# 10MHzRefOsc_2V3.net
KiCad netlist of a schematic drawn in EAGLE
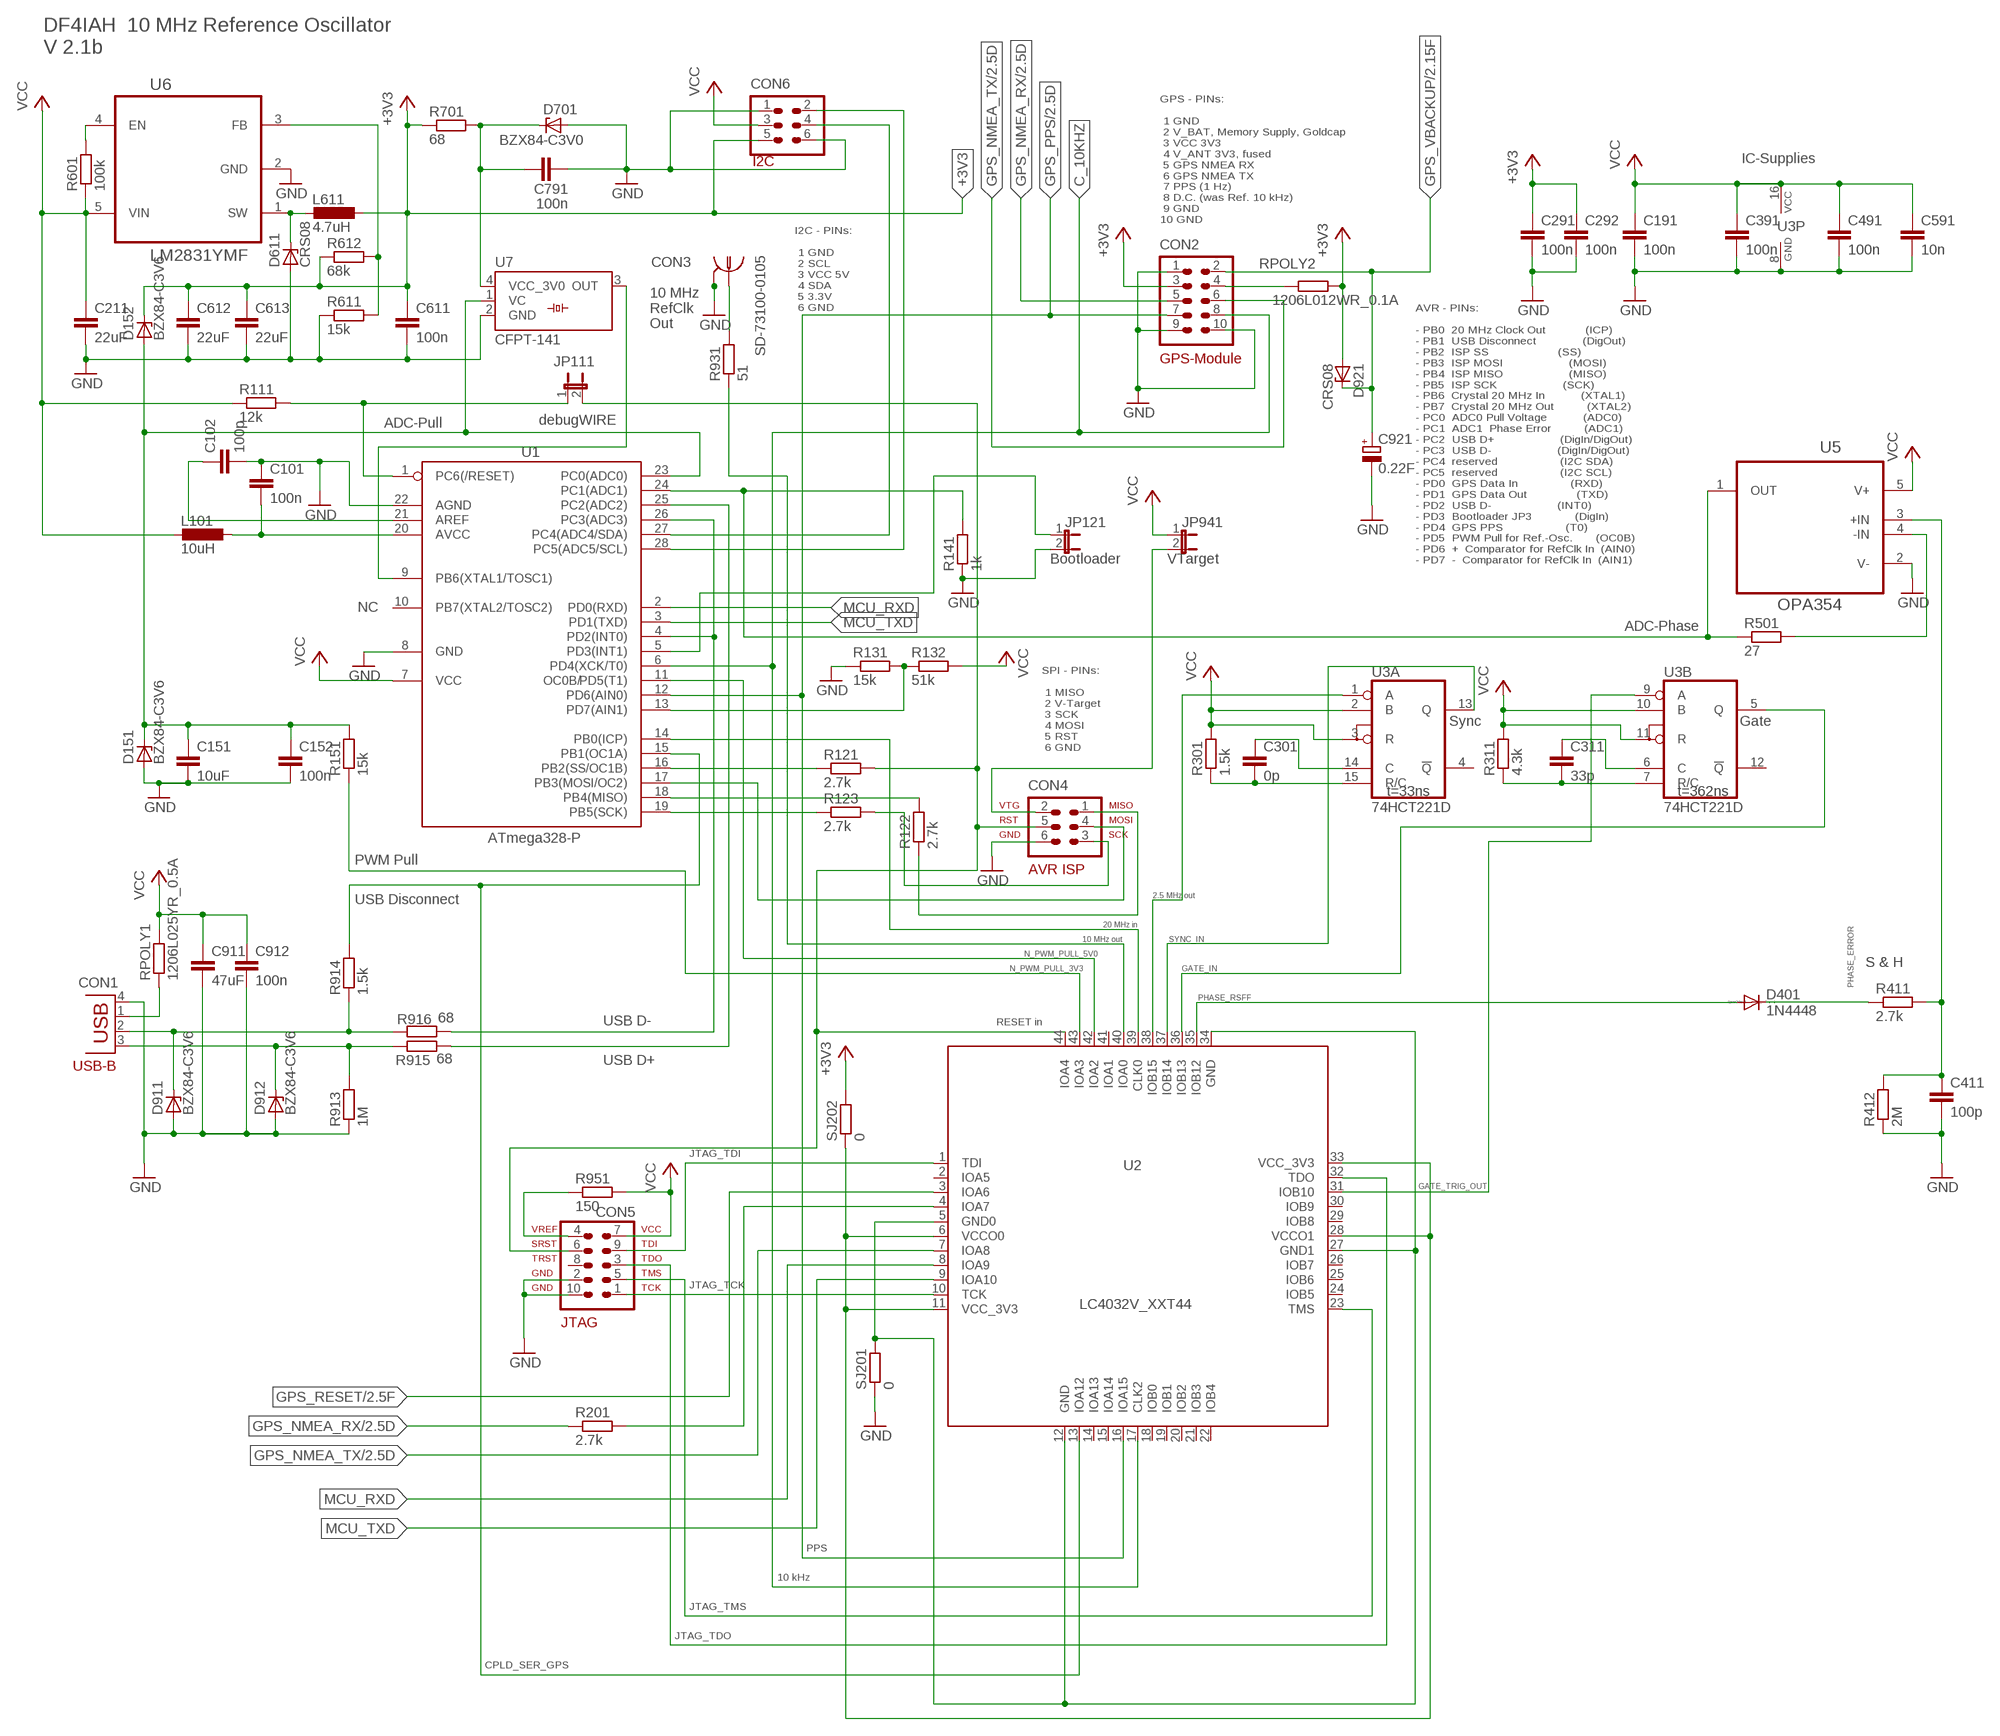
[diagram p0: schematic, sheet 1]
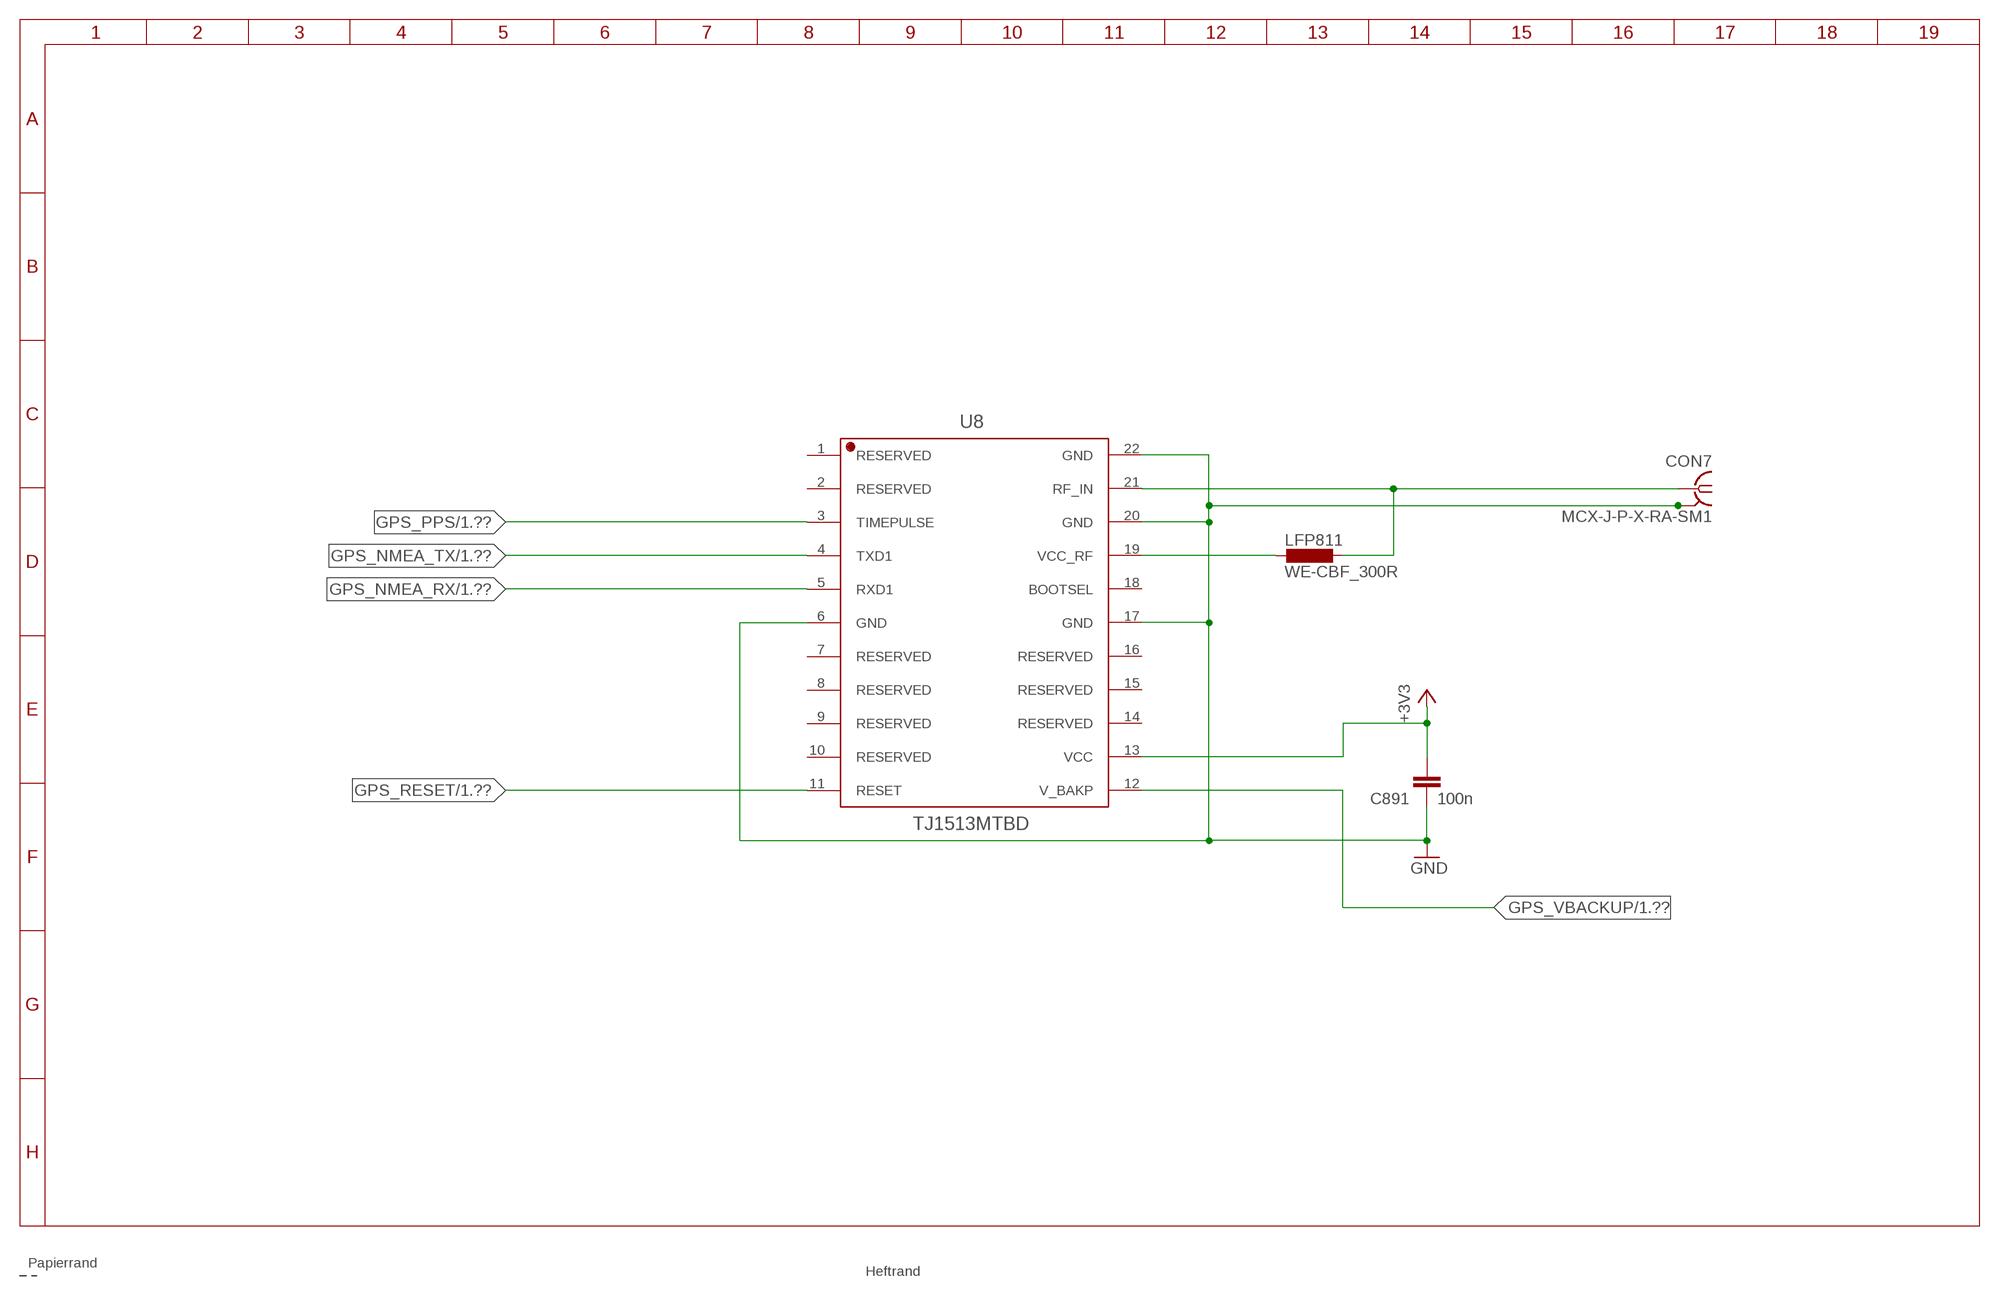
[diagram p1: schematic, sheet 2]
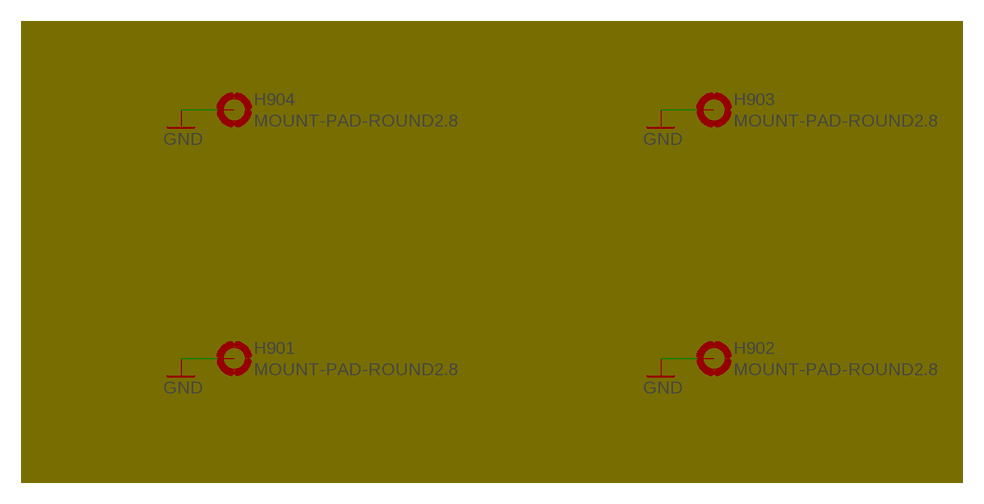
[diagram p2: schematic, sheet 3]

(export (version "E")
  (design (tool "Eeschema 10.0.6"))
  (components
    (comp (ref "H901")
      (value "MOUNT-PAD-ROUND2.8")
      (footprint "eagle-import:2,8-PAD")
      (libsource (lib "eagle-import") (part "MOUNT-PAD-ROUND2.8"))
    )
    (comp (ref "H902")
      (value "MOUNT-PAD-ROUND2.8")
      (footprint "eagle-import:2,8-PAD")
      (libsource (lib "eagle-import") (part "MOUNT-PAD-ROUND2.8"))
    )
    (comp (ref "H903")
      (value "MOUNT-PAD-ROUND2.8")
      (footprint "eagle-import:2,8-PAD")
      (libsource (lib "eagle-import") (part "MOUNT-PAD-ROUND2.8"))
    )
    (comp (ref "H904")
      (value "MOUNT-PAD-ROUND2.8")
      (footprint "eagle-import:2,8-PAD")
      (libsource (lib "eagle-import") (part "MOUNT-PAD-ROUND2.8"))
    )
    (comp (ref "C891")
      (value "100n")
      (footprint "eagle-import:C0805")
      (libsource (lib "eagle-import") (part "C-EUC0805"))
    )
    (comp (ref "CON7")
      (value "MCX-J-P-X-RA-SM1")
      (footprint "eagle-import:MCX-J-P-X-RA-SM1")
      (libsource (lib "eagle-import") (part "MCX-J-P-X-RA-SM1"))
    )
    (comp (ref "LFP811")
      (value "WE-CBF_300R")
      (footprint "eagle-import:L3216C")
      (libsource (lib "eagle-import") (part "L-EUL3216C"))
    )
    (comp (ref "U8")
      (value "TJ1513MTBD")
      (footprint "eagle-import:TJ1513MTBD")
      (libsource (lib "eagle-import") (part "TJ1513MTBD"))
    )
    (comp (ref "C101")
      (value "100n")
      (footprint "eagle-import:C0805")
      (libsource (lib "eagle-import") (part "rcl_C-EUC0805"))
    )
    (comp (ref "C102")
      (value "100p")
      (footprint "eagle-import:C0805")
      (libsource (lib "eagle-import") (part "rcl_C-EUC0805"))
    )
    (comp (ref "C151")
      (value "10uF")
      (footprint "eagle-import:C0805")
      (libsource (lib "eagle-import") (part "rcl_C-EUC0805"))
    )
    (comp (ref "C152")
      (value "100n")
      (footprint "eagle-import:C0805")
      (libsource (lib "eagle-import") (part "rcl_C-EUC0805"))
    )
    (comp (ref "C191")
      (value "100n")
      (footprint "eagle-import:C0805")
      (libsource (lib "eagle-import") (part "rcl_C-EUC0805"))
    )
    (comp (ref "C211")
      (value "22uF")
      (footprint "eagle-import:C0805")
      (libsource (lib "eagle-import") (part "rcl_C-EUC0805"))
    )
    (comp (ref "C291")
      (value "100n")
      (footprint "eagle-import:C0805")
      (libsource (lib "eagle-import") (part "rcl_C-EUC0805"))
    )
    (comp (ref "C292")
      (value "100n")
      (footprint "eagle-import:C0805")
      (libsource (lib "eagle-import") (part "rcl_C-EUC0805"))
    )
    (comp (ref "C301")
      (value "0p")
      (footprint "eagle-import:C0805")
      (libsource (lib "eagle-import") (part "rcl_C-EUC0805"))
    )
    (comp (ref "C311")
      (value "33p")
      (footprint "eagle-import:C0805")
      (libsource (lib "eagle-import") (part "rcl_C-EUC0805"))
    )
    (comp (ref "C391")
      (value "100n")
      (footprint "eagle-import:C0805")
      (libsource (lib "eagle-import") (part "rcl_C-EUC0805"))
    )
    (comp (ref "C411")
      (value "100p")
      (footprint "eagle-import:C0805")
      (libsource (lib "eagle-import") (part "rcl_C-EUC0805"))
    )
    (comp (ref "C491")
      (value "100n")
      (footprint "eagle-import:C0805")
      (libsource (lib "eagle-import") (part "rcl_C-EUC0805"))
    )
    (comp (ref "C591")
      (value "10n")
      (footprint "eagle-import:C0805")
      (libsource (lib "eagle-import") (part "rcl_C-EUC0805"))
    )
    (comp (ref "C611")
      (value "100n")
      (footprint "eagle-import:C0805")
      (libsource (lib "eagle-import") (part "rcl_C-EUC0805"))
    )
    (comp (ref "C612")
      (value "22uF")
      (footprint "eagle-import:C0805")
      (libsource (lib "eagle-import") (part "rcl_C-EUC0805"))
    )
    (comp (ref "C613")
      (value "22uF")
      (footprint "eagle-import:C0805")
      (libsource (lib "eagle-import") (part "rcl_C-EUC0805"))
    )
    (comp (ref "C791")
      (value "100n")
      (footprint "eagle-import:C0805")
      (libsource (lib "eagle-import") (part "rcl_C-EUC0805"))
    )
    (comp (ref "C911")
      (value "47uF")
      (footprint "eagle-import:C0805")
      (libsource (lib "eagle-import") (part "rcl_C-EUC0805"))
    )
    (comp (ref "C912")
      (value "100n")
      (footprint "eagle-import:C0805")
      (libsource (lib "eagle-import") (part "rcl_C-EUC0805"))
    )
    (comp (ref "C921")
      (value "0.22F")
      (footprint "eagle-import:140CLH-1010")
      (libsource (lib "eagle-import") (part "CPOL-EU140CLH-1010"))
    )
    (comp (ref "CON1")
      (value "TYCO-AMP_USBUSB-B_SMT")
      (footprint "eagle-import:TYCO-AMP_USB-B_SMT")
      (fields (field (name "MF") "TYCO-AMP") (field (name "MPN") "1734346"))
      (libsource (lib "eagle-import") (part "TYCO-AMP_USBUSB-B_SMT"))
    )
    (comp (ref "CON2")
      (value "HEADER-2X5SMD")
      (footprint "eagle-import:2X5SMD")
      (libsource (lib "eagle-import") (part "HEADER-2X5SMD"))
    )
    (comp (ref "CON3")
      (value "SD-73100-0105")
      (footprint "eagle-import:MOLEX_BNC-JACK-50R_SD-73100-0105")
      (fields (field (name "MF") "MOLEX"))
      (libsource (lib "eagle-import") (part "MOLEX_BNC-JACK-50R_SD-73100-0105"))
    )
    (comp (ref "CON4")
      (value "AVR-ISP-6SMD")
      (footprint "eagle-import:2X3SMD")
      (libsource (lib "eagle-import") (part "AVR-ISP-6SMD"))
    )
    (comp (ref "CON5")
      (value "AVR-JTAG-10SMD")
      (footprint "eagle-import:2X5SMD")
      (libsource (lib "eagle-import") (part "AVR-JTAG-10SMD"))
    )
    (comp (ref "CON6")
      (value "HEADER-2X3SMD")
      (footprint "eagle-import:2X03SMD")
      (libsource (lib "eagle-import") (part "HEADER-2X3SMD"))
    )
    (comp (ref "D151")
      (value "BZX84-C3V6")
      (footprint "eagle-import:TO236")
      (libsource (lib "eagle-import") (part "BZX84CSMD"))
    )
    (comp (ref "D152")
      (value "BZX84-C3V6")
      (footprint "eagle-import:TO236")
      (libsource (lib "eagle-import") (part "BZX84CSMD"))
    )
    (comp (ref "D401")
      (value "1N4448")
      (footprint "eagle-import:SOD123")
      (libsource (lib "eagle-import") (part "DIODE-SOD123"))
    )
    (comp (ref "D611")
      (value "CRS08")
      (footprint "eagle-import:SOD80C")
      (libsource (lib "eagle-import") (part "ZENER-DIODESOD80C"))
    )
    (comp (ref "D701")
      (value "BZX84-C3V0")
      (footprint "eagle-import:TO236")
      (libsource (lib "eagle-import") (part "BZX84CSMD"))
    )
    (comp (ref "D911")
      (value "BZX84-C3V6")
      (footprint "eagle-import:TO236")
      (libsource (lib "eagle-import") (part "BZX84CSMD"))
    )
    (comp (ref "D912")
      (value "BZX84-C3V6")
      (footprint "eagle-import:TO236")
      (libsource (lib "eagle-import") (part "BZX84CSMD"))
    )
    (comp (ref "D921")
      (value "CRS08")
      (footprint "eagle-import:SOD80C")
      (libsource (lib "eagle-import") (part "ZENER-DIODESOD80C"))
    )
    (comp (ref "JP111")
      (value "JP1E")
      (footprint "eagle-import:JP1")
      (libsource (lib "eagle-import") (part "JP1E"))
    )
    (comp (ref "JP121")
      (value "JP1E")
      (footprint "eagle-import:JP1")
      (libsource (lib "eagle-import") (part "JP1E"))
    )
    (comp (ref "JP941")
      (value "JP1E")
      (footprint "eagle-import:JP1")
      (libsource (lib "eagle-import") (part "JP1E"))
    )
    (comp (ref "L101")
      (value "10uH")
      (footprint "eagle-import:L1812")
      (libsource (lib "eagle-import") (part "rcl_L-EUL1812"))
    )
    (comp (ref "L611")
      (value "4.7uH")
      (footprint "eagle-import:L5650M")
      (libsource (lib "eagle-import") (part "rcl_L-EUL5650M"))
    )
    (comp (ref "R111")
      (value "12k")
      (footprint "eagle-import:R0805")
      (libsource (lib "eagle-import") (part "R-EU_R0805"))
    )
    (comp (ref "R121")
      (value "2.7k")
      (footprint "eagle-import:R0805")
      (libsource (lib "eagle-import") (part "R-EU_R0805"))
    )
    (comp (ref "R122")
      (value "2.7k")
      (footprint "eagle-import:R0805")
      (libsource (lib "eagle-import") (part "R-EU_R0805"))
    )
    (comp (ref "R123")
      (value "2.7k")
      (footprint "eagle-import:R0805")
      (libsource (lib "eagle-import") (part "R-EU_R0805"))
    )
    (comp (ref "R131")
      (value "15k")
      (footprint "eagle-import:R0805")
      (libsource (lib "eagle-import") (part "R-EU_R0805"))
    )
    (comp (ref "R132")
      (value "51k")
      (footprint "eagle-import:R0805")
      (libsource (lib "eagle-import") (part "R-EU_R0805"))
    )
    (comp (ref "R141")
      (value "1k")
      (footprint "eagle-import:R0805")
      (libsource (lib "eagle-import") (part "R-EU_R0805"))
    )
    (comp (ref "R151")
      (value "15k")
      (footprint "eagle-import:R0805")
      (libsource (lib "eagle-import") (part "R-EU_R0805"))
    )
    (comp (ref "R201")
      (value "2.7k")
      (footprint "eagle-import:R0805")
      (libsource (lib "eagle-import") (part "R-EU_R0805"))
    )
    (comp (ref "R301")
      (value "1.5k")
      (footprint "eagle-import:R0805")
      (libsource (lib "eagle-import") (part "R-EU_R0805"))
    )
    (comp (ref "R311")
      (value "4.3k")
      (footprint "eagle-import:R0805")
      (libsource (lib "eagle-import") (part "R-EU_R0805"))
    )
    (comp (ref "R411")
      (value "2.7k")
      (footprint "eagle-import:R0805")
      (libsource (lib "eagle-import") (part "R-EU_R0805"))
    )
    (comp (ref "R412")
      (value "2M")
      (footprint "eagle-import:R0805")
      (libsource (lib "eagle-import") (part "R-EU_R0805"))
    )
    (comp (ref "R501")
      (value "27")
      (footprint "eagle-import:R0805")
      (libsource (lib "eagle-import") (part "R-EU_R0805"))
    )
    (comp (ref "R601")
      (value "100k")
      (footprint "eagle-import:R0805")
      (libsource (lib "eagle-import") (part "R-EU_R0805"))
    )
    (comp (ref "R611")
      (value "15k")
      (footprint "eagle-import:R0805")
      (libsource (lib "eagle-import") (part "R-EU_R0805"))
    )
    (comp (ref "R612")
      (value "68k")
      (footprint "eagle-import:R0805")
      (libsource (lib "eagle-import") (part "R-EU_R0805"))
    )
    (comp (ref "R701")
      (value "68")
      (footprint "eagle-import:R0805")
      (libsource (lib "eagle-import") (part "R-EU_R0805"))
    )
    (comp (ref "R913")
      (value "1M")
      (footprint "eagle-import:R0805")
      (libsource (lib "eagle-import") (part "R-EU_R0805"))
    )
    (comp (ref "R914")
      (value "1.5k")
      (footprint "eagle-import:R0805")
      (libsource (lib "eagle-import") (part "R-EU_R0805"))
    )
    (comp (ref "R915")
      (value "68")
      (footprint "eagle-import:R0805")
      (libsource (lib "eagle-import") (part "R-EU_R0805"))
    )
    (comp (ref "R916")
      (value "68")
      (footprint "eagle-import:R0805")
      (libsource (lib "eagle-import") (part "R-EU_R0805"))
    )
    (comp (ref "R931")
      (value "51")
      (footprint "eagle-import:R0805")
      (libsource (lib "eagle-import") (part "R-EU_R0805"))
    )
    (comp (ref "R951")
      (value "150")
      (footprint "eagle-import:R0805")
      (libsource (lib "eagle-import") (part "R-EU_R0805"))
    )
    (comp (ref "RPOLY1")
      (value "1206L025YR_0.5A")
      (footprint "eagle-import:M1206")
      (libsource (lib "eagle-import") (part "R-EU_M1206"))
    )
    (comp (ref "RPOLY2")
      (value "1206L012WR_0.1A")
      (footprint "eagle-import:M1206")
      (libsource (lib "eagle-import") (part "R-EU_M1206"))
    )
    (comp (ref "SJ201")
      (value "0")
      (footprint "eagle-import:R0805")
      (libsource (lib "eagle-import") (part "R-EU_R0805"))
    )
    (comp (ref "SJ202")
      (value "0")
      (footprint "eagle-import:R0805")
      (libsource (lib "eagle-import") (part "R-EU_R0805"))
    )
    (comp (ref "U1")
      (value "ATmega328-P")
      (footprint "eagle-import:DIL28-3")
      (libsource (lib "eagle-import") (part "MEGA8-P"))
    )
    (comp (ref "U2")
      (value "LC4032V_XXT44")
      (footprint "eagle-import:TQFP44")
      (libsource (lib "eagle-import") (part "LC4032V_XXT44"))
    )
    (comp (ref "U3")
      (value "74HCT221D")
      (footprint "eagle-import:SO16")
      (libsource (lib "eagle-import") (part "74221DHCT"))
    )
    (comp (ref "U5")
      (value "OPA354")
      (footprint "eagle-import:SOT-23-5")
      (fields (field (name "MPN") "OPA354AIDBVT"))
      (libsource (lib "eagle-import") (part "OPA354"))
    )
    (comp (ref "U6")
      (value "LM2831YMF")
      (footprint "eagle-import:SOT95P280X145-5N")
      (fields (field (name "MPN") "LM2831YMF/NOPB"))
      (libsource (lib "eagle-import") (part "LM2831YMF"))
    )
    (comp (ref "U7")
      (value "CFPT-141")
      (footprint "eagle-import:CFPT-141")
      (fields (field (name "MF") "IQD-FREQUENCY-PRODUCTS") (field (name "MPN") "LFTVXO022175"))
      (libsource (lib "eagle-import") (part "CFPT-141"))
    )
  )
  (nets
    (net (code "1") (name "+3V3") (class "Default")
      (node (ref "C291") (pin "1") (pinfunction "1_1") (pintype "passive"))
      (node (ref "C292") (pin "1") (pinfunction "1_1") (pintype "passive"))
      (node (ref "C611") (pin "1") (pinfunction "1_1") (pintype "passive"))
      (node (ref "C612") (pin "1") (pinfunction "1_1") (pintype "passive"))
      (node (ref "C613") (pin "1") (pinfunction "1_1") (pintype "passive"))
      (node (ref "C891") (pin "1") (pinfunction "1_1") (pintype "passive"))
      (node (ref "CON2") (pin "3") (pinfunction "3_3") (pintype "passive"))
      (node (ref "CON6") (pin "5") (pinfunction "5_5") (pintype "passive"))
      (node (ref "D152") (pin "C") (pinfunction "C_C") (pintype "passive"))
      (node (ref "D921") (pin "A") (pinfunction "A_A") (pintype "passive"))
      (node (ref "L611") (pin "1") (pinfunction "1_1") (pintype "passive"))
      (node (ref "R612") (pin "1") (pinfunction "1_1") (pintype "passive"))
      (node (ref "R701") (pin "1") (pinfunction "1_1") (pintype "passive"))
      (node (ref "RPOLY2") (pin "2") (pinfunction "2_2") (pintype "passive"))
      (node (ref "SJ202") (pin "2") (pinfunction "2_2") (pintype "passive"))
      (node (ref "U8") (pin "13") (pinfunction "VCC_13") (pintype "power_in"))
    )
    (net (code "2") (name "C_10KHZ") (class "Default")
      (node (ref "CON2") (pin "8") (pinfunction "8_8") (pintype "passive"))
      (node (ref "U1") (pin "6") (pinfunction "PD4(XCK/T0)_6") (pintype "bidirectional"))
      (node (ref "U2") (pin "17") (pinfunction "CLK2_17") (pintype "input"))
    )
    (net (code "3") (name "GATE_IN") (class "Default")
      (node (ref "U2") (pin "36") (pinfunction "IOB13_36") (pintype "bidirectional"))
      (node (ref "U3") (pin "5") (pinfunction "Q_5") (pintype "output"))
    )
    (net (code "4") (name "GATE_TRIG_OUT") (class "Default")
      (node (ref "U2") (pin "31") (pinfunction "IOB10_31") (pintype "bidirectional"))
      (node (ref "U3") (pin "9") (pinfunction "A_9") (pintype "input"))
    )
    (net (code "5") (name "GND") (class "Default")
      (node (ref "C101") (pin "1") (pinfunction "1_1") (pintype "passive"))
      (node (ref "C102") (pin "2") (pinfunction "2_2") (pintype "passive"))
      (node (ref "C151") (pin "2") (pinfunction "2_2") (pintype "passive"))
      (node (ref "C152") (pin "2") (pinfunction "2_2") (pintype "passive"))
      (node (ref "C191") (pin "2") (pinfunction "2_2") (pintype "passive"))
      (node (ref "C211") (pin "2") (pinfunction "2_2") (pintype "passive"))
      (node (ref "C291") (pin "2") (pinfunction "2_2") (pintype "passive"))
      (node (ref "C292") (pin "2") (pinfunction "2_2") (pintype "passive"))
      (node (ref "C391") (pin "2") (pinfunction "2_2") (pintype "passive"))
      (node (ref "C411") (pin "2") (pinfunction "2_2") (pintype "passive"))
      (node (ref "C491") (pin "2") (pinfunction "2_2") (pintype "passive"))
      (node (ref "C591") (pin "2") (pinfunction "2_2") (pintype "passive"))
      (node (ref "C611") (pin "2") (pinfunction "2_2") (pintype "passive"))
      (node (ref "C612") (pin "2") (pinfunction "2_2") (pintype "passive"))
      (node (ref "C613") (pin "2") (pinfunction "2_2") (pintype "passive"))
      (node (ref "C791") (pin "2") (pinfunction "2_2") (pintype "passive"))
      (node (ref "C891") (pin "2") (pinfunction "2_2") (pintype "passive"))
      (node (ref "C911") (pin "2") (pinfunction "2_2") (pintype "passive"))
      (node (ref "C912") (pin "2") (pinfunction "2_2") (pintype "passive"))
      (node (ref "C921") (pin "-") (pinfunction "-_-") (pintype "passive"))
      (node (ref "CON1") (pin "4") (pinfunction "GND_4") (pintype "bidirectional"))
      (node (ref "CON2") (pin "1") (pinfunction "1_1") (pintype "passive"))
      (node (ref "CON2") (pin "10") (pinfunction "10_10") (pintype "passive"))
      (node (ref "CON2") (pin "9") (pinfunction "9_9") (pintype "passive"))
      (node (ref "CON3") (pin "2") (pinfunction "2_2") (pintype "passive"))
      (node (ref "CON3") (pin "3") (pinfunction "3_3") (pintype "passive"))
      (node (ref "CON4") (pin "6") (pinfunction "6_6") (pintype "passive"))
      (node (ref "CON5") (pin "10") (pinfunction "10_10") (pintype "passive"))
      (node (ref "CON5") (pin "2") (pinfunction "2_2") (pintype "passive"))
      (node (ref "CON6") (pin "1") (pinfunction "1_1") (pintype "passive"))
      (node (ref "CON6") (pin "6") (pinfunction "6_6") (pintype "passive"))
      (node (ref "CON7") (pin "2") (pinfunction "2_2") (pintype "passive"))
      (node (ref "CON7") (pin "3") (pinfunction "3_3") (pintype "passive"))
      (node (ref "CON7") (pin "4") (pinfunction "4_4") (pintype "passive"))
      (node (ref "CON7") (pin "5") (pinfunction "5_5") (pintype "passive"))
      (node (ref "D151") (pin "A") (pinfunction "A_A") (pintype "passive"))
      (node (ref "D611") (pin "A") (pinfunction "A_A") (pintype "passive"))
      (node (ref "D701") (pin "A") (pinfunction "A_A") (pintype "passive"))
      (node (ref "D911") (pin "A") (pinfunction "A_A") (pintype "passive"))
      (node (ref "D912") (pin "A") (pinfunction "A_A") (pintype "passive"))
      (node (ref "H901") (pin "B2,8") (pinfunction "MOUNT_B2,8") (pintype "passive"))
      (node (ref "H902") (pin "B2,8") (pinfunction "MOUNT_B2,8") (pintype "passive"))
      (node (ref "H903") (pin "B2,8") (pinfunction "MOUNT_B2,8") (pintype "passive"))
      (node (ref "H904") (pin "B2,8") (pinfunction "MOUNT_B2,8") (pintype "passive"))
      (node (ref "JP121") (pin "2") (pinfunction "2_2") (pintype "passive"))
      (node (ref "R131") (pin "1") (pinfunction "1_1") (pintype "passive"))
      (node (ref "R141") (pin "1") (pinfunction "1_1") (pintype "passive"))
      (node (ref "R412") (pin "1") (pinfunction "1_1") (pintype "passive"))
      (node (ref "R611") (pin "1") (pinfunction "1_1") (pintype "passive"))
      (node (ref "R913") (pin "1") (pinfunction "1_1") (pintype "passive"))
      (node (ref "SJ201") (pin "1") (pinfunction "1_1") (pintype "passive"))
      (node (ref "U1") (pin "22") (pinfunction "AGND_22") (pintype "bidirectional"))
      (node (ref "U1") (pin "8") (pinfunction "GND_8") (pintype "bidirectional"))
      (node (ref "U3") (pin "8") (pinfunction "GND_8") (pintype "power_in"))
      (node (ref "U5") (pin "2") (pinfunction "V-_2") (pintype "power_in"))
      (node (ref "U6") (pin "2") (pinfunction "GND_2") (pintype "passive"))
      (node (ref "U7") (pin "2") (pinfunction "GND_2") (pintype "power_in"))
      (node (ref "U8") (pin "17") (pinfunction "GND_17") (pintype "power_in"))
      (node (ref "U8") (pin "20") (pinfunction "GND_20") (pintype "power_in"))
      (node (ref "U8") (pin "22") (pinfunction "GND_22") (pintype "power_in"))
      (node (ref "U8") (pin "6") (pinfunction "GND_6") (pintype "power_in"))
    )
    (net (code "6") (name "GPS_NMEA_RX") (class "Default")
      (node (ref "CON2") (pin "5") (pinfunction "5_5") (pintype "passive"))
      (node (ref "R201") (pin "1") (pinfunction "1_1") (pintype "passive"))
      (node (ref "U8") (pin "5") (pinfunction "RXD1_5") (pintype "input"))
    )
    (net (code "7") (name "GPS_NMEA_TX") (class "Default")
      (node (ref "CON2") (pin "6") (pinfunction "6_6") (pintype "passive"))
      (node (ref "U2") (pin "7") (pinfunction "IOA8_7") (pintype "bidirectional"))
      (node (ref "U8") (pin "4") (pinfunction "TXD1_4") (pintype "output"))
    )
    (net (code "8") (name "GPS_PPS") (class "Default")
      (node (ref "CON2") (pin "7") (pinfunction "7_7") (pintype "passive"))
      (node (ref "U1") (pin "12") (pinfunction "PD6(AIN0)_12") (pintype "bidirectional"))
      (node (ref "U2") (pin "16") (pinfunction "IOA15_16") (pintype "bidirectional"))
      (node (ref "U8") (pin "3") (pinfunction "TIMEPULSE_3") (pintype "output"))
    )
    (net (code "9") (name "GPS_RESET") (class "Default")
      (node (ref "U2") (pin "3") (pinfunction "IOA6_3") (pintype "bidirectional"))
      (node (ref "U8") (pin "11") (pinfunction "RESET_11") (pintype "passive"))
    )
    (net (code "10") (name "GPS_VBACKUP") (class "Default")
      (node (ref "C921") (pin "+") (pinfunction "+_+") (pintype "passive"))
      (node (ref "CON2") (pin "2") (pinfunction "2_2") (pintype "passive"))
      (node (ref "D921") (pin "C") (pinfunction "C_C") (pintype "passive"))
      (node (ref "U8") (pin "12") (pinfunction "V_BAKP_12") (pintype "power_in"))
    )
    (net (code "11") (name "MCU_RXD") (class "Default")
      (node (ref "U1") (pin "2") (pinfunction "PD0(RXD)_2") (pintype "bidirectional"))
      (node (ref "U2") (pin "8") (pinfunction "IOA9_8") (pintype "bidirectional"))
    )
    (net (code "12") (name "MCU_TXD") (class "Default")
      (node (ref "U1") (pin "3") (pinfunction "PD1(TXD)_3") (pintype "bidirectional"))
      (node (ref "U2") (pin "9") (pinfunction "IOA10_9") (pintype "bidirectional"))
    )
    (net (code "13") (name "N_PWM_PULL_3V3") (class "Default")
      (node (ref "R151") (pin "1") (pinfunction "1_1") (pintype "passive"))
      (node (ref "U2") (pin "43") (pinfunction "IOA3_43") (pintype "bidirectional"))
    )
    (net (code "14") (name "N_PWM_PULL_5V0") (class "Default")
      (node (ref "U1") (pin "11") (pinfunction "PD5(T1)_11") (pintype "bidirectional"))
      (node (ref "U2") (pin "42") (pinfunction "IOA2_42") (pintype "bidirectional"))
    )
    (net (code "15") (name "Net-(CON1-D+)") (class "Default")
      (node (ref "CON1") (pin "3") (pinfunction "D+_3") (pintype "bidirectional"))
      (node (ref "D912") (pin "C") (pinfunction "C_C") (pintype "passive"))
      (node (ref "R913") (pin "2") (pinfunction "2_2") (pintype "passive"))
      (node (ref "R915") (pin "1") (pinfunction "1_1") (pintype "passive"))
    )
    (net (code "16") (name "Net-(CON1-D-)") (class "Default")
      (node (ref "CON1") (pin "2") (pinfunction "D-_2") (pintype "bidirectional"))
      (node (ref "D911") (pin "C") (pinfunction "C_C") (pintype "passive"))
      (node (ref "R914") (pin "1") (pinfunction "1_1") (pintype "passive"))
      (node (ref "R916") (pin "1") (pinfunction "1_1") (pintype "passive"))
    )
    (net (code "17") (name "Net-(CON1-VBUS)") (class "Default")
      (node (ref "CON1") (pin "1") (pinfunction "VBUS_1") (pintype "bidirectional"))
      (node (ref "RPOLY1") (pin "1") (pinfunction "1_1") (pintype "passive"))
    )
    (net (code "18") (name "Net-(CON2-Pad4)") (class "Default")
      (node (ref "CON2") (pin "4") (pinfunction "4_4") (pintype "passive"))
      (node (ref "RPOLY2") (pin "1") (pinfunction "1_1") (pintype "passive"))
    )
    (net (code "19") (name "Net-(CON3-Pad1)") (class "Default")
      (node (ref "CON3") (pin "1") (pinfunction "1_1") (pintype "passive"))
      (node (ref "R931") (pin "2") (pinfunction "2_2") (pintype "passive"))
    )
    (net (code "20") (name "Net-(CON4-Pad1)") (class "Default")
      (node (ref "CON4") (pin "1") (pinfunction "1_1") (pintype "passive"))
      (node (ref "R122") (pin "1") (pinfunction "1_1") (pintype "passive"))
    )
    (net (code "21") (name "Net-(CON4-Pad2)") (class "Default")
      (node (ref "CON4") (pin "2") (pinfunction "2_2") (pintype "passive"))
      (node (ref "JP941") (pin "2") (pinfunction "2_2") (pintype "passive"))
    )
    (net (code "22") (name "Net-(CON4-Pad3)") (class "Default")
      (node (ref "CON4") (pin "3") (pinfunction "3_3") (pintype "passive"))
      (node (ref "R123") (pin "2") (pinfunction "2_2") (pintype "passive"))
    )
    (net (code "23") (name "Net-(CON5-Pad4)") (class "Default")
      (node (ref "CON5") (pin "4") (pinfunction "4_4") (pintype "passive"))
      (node (ref "R951") (pin "1") (pinfunction "1_1") (pintype "passive"))
    )
    (net (code "24") (name "Net-(U1-AREF)") (class "Default")
      (node (ref "C102") (pin "1") (pinfunction "1_1") (pintype "passive"))
      (node (ref "U1") (pin "21") (pinfunction "AREF_21") (pintype "bidirectional"))
    )
    (net (code "25") (name "Net-(U1-AVCC)") (class "Default")
      (node (ref "C101") (pin "2") (pinfunction "2_2") (pintype "passive"))
      (node (ref "L101") (pin "1") (pinfunction "1_1") (pintype "passive"))
      (node (ref "U1") (pin "20") (pinfunction "AVCC_20") (pintype "bidirectional"))
    )
    (net (code "26") (name "Net-(U1-PB0(ICP))") (class "Default")
      (node (ref "U1") (pin "14") (pinfunction "PB0(ICP)_14") (pintype "bidirectional"))
      (node (ref "U2") (pin "39") (pinfunction "CLK0_39") (pintype "input"))
    )
    (net (code "27") (name "Net-(U1-PB1(OC1A))") (class "Default")
      (node (ref "R914") (pin "2") (pinfunction "2_2") (pintype "passive"))
      (node (ref "U1") (pin "15") (pinfunction "PB1(OC1A)_15") (pintype "bidirectional"))
      (node (ref "U2") (pin "13") (pinfunction "IOA12_13") (pintype "bidirectional"))
    )
    (net (code "28") (name "Net-(U1-PB2(SS{slash}OC1B))") (class "Default")
      (node (ref "R121") (pin "1") (pinfunction "1_1") (pintype "passive"))
      (node (ref "U1") (pin "16") (pinfunction "PB2(SS/OC1B)_16") (pintype "bidirectional"))
    )
    (net (code "29") (name "Net-(U1-PB3(MOSI{slash}OC2))") (class "Default")
      (node (ref "CON4") (pin "4") (pinfunction "4_4") (pintype "passive"))
      (node (ref "U1") (pin "17") (pinfunction "PB3(MOSI/OC2)_17") (pintype "bidirectional"))
    )
    (net (code "30") (name "Net-(U1-PB4(MISO))") (class "Default")
      (node (ref "R122") (pin "2") (pinfunction "2_2") (pintype "passive"))
      (node (ref "U1") (pin "18") (pinfunction "PB4(MISO)_18") (pintype "bidirectional"))
    )
    (net (code "31") (name "Net-(U1-PB5(SCK))") (class "Default")
      (node (ref "R123") (pin "1") (pinfunction "1_1") (pintype "passive"))
      (node (ref "U1") (pin "19") (pinfunction "PB5(SCK)_19") (pintype "bidirectional"))
    )
    (net (code "32") (name "Net-(U1-PB6(XTAL1{slash}TOSC1))") (class "Default")
      (node (ref "U1") (pin "9") (pinfunction "PB6(XTAL1/TOSC1)_9") (pintype "bidirectional"))
      (node (ref "U7") (pin "3") (pinfunction "OUT_3") (pintype "output"))
    )
    (net (code "33") (name "Net-(U1-PC0(ADC0))") (class "Default")
      (node (ref "C151") (pin "1") (pinfunction "1_1") (pintype "passive"))
      (node (ref "C152") (pin "1") (pinfunction "1_1") (pintype "passive"))
      (node (ref "D151") (pin "C") (pinfunction "C_C") (pintype "passive"))
      (node (ref "D152") (pin "A") (pinfunction "A_A") (pintype "passive"))
      (node (ref "R151") (pin "2") (pinfunction "2_2") (pintype "passive"))
      (node (ref "U1") (pin "23") (pinfunction "PC0(ADC0)_23") (pintype "bidirectional"))
      (node (ref "U7") (pin "1") (pinfunction "VC_1") (pintype "input"))
    )
    (net (code "34") (name "Net-(U1-PC1(ADC1))") (class "Default")
      (node (ref "R141") (pin "2") (pinfunction "2_2") (pintype "passive"))
      (node (ref "R501") (pin "1") (pinfunction "1_1") (pintype "passive"))
      (node (ref "U1") (pin "24") (pinfunction "PC1(ADC1)_24") (pintype "bidirectional"))
      (node (ref "U5") (pin "1") (pinfunction "OUT_1") (pintype "output"))
    )
    (net (code "35") (name "Net-(U1-PC2(ADC2))") (class "Default")
      (node (ref "R915") (pin "2") (pinfunction "2_2") (pintype "passive"))
      (node (ref "U1") (pin "25") (pinfunction "PC2(ADC2)_25") (pintype "bidirectional"))
    )
    (net (code "36") (name "Net-(U1-PC3(ADC3))") (class "Default")
      (node (ref "R916") (pin "2") (pinfunction "2_2") (pintype "passive"))
      (node (ref "U1") (pin "26") (pinfunction "PC3(ADC3)_26") (pintype "bidirectional"))
      (node (ref "U1") (pin "4") (pinfunction "PD2(INT0)_4") (pintype "bidirectional"))
    )
    (net (code "37") (name "Net-(U1-PC4(ADC4{slash}SDA))") (class "Default")
      (node (ref "CON6") (pin "4") (pinfunction "4_4") (pintype "passive"))
      (node (ref "U1") (pin "27") (pinfunction "PC4(ADC4/SDA)_27") (pintype "bidirectional"))
    )
    (net (code "38") (name "Net-(U1-PC5(ADC5{slash}SCL))") (class "Default")
      (node (ref "CON6") (pin "2") (pinfunction "2_2") (pintype "passive"))
      (node (ref "U1") (pin "28") (pinfunction "PC5(ADC5/SCL)_28") (pintype "bidirectional"))
    )
    (net (code "39") (name "Net-(U1-PC6({slash}RESET))") (class "Default")
      (node (ref "JP111") (pin "1") (pinfunction "1_1") (pintype "passive"))
      (node (ref "R111") (pin "2") (pinfunction "2_2") (pintype "passive"))
      (node (ref "U1") (pin "1") (pinfunction "PC6(/RESET)_1") (pintype "bidirectional"))
    )
    (net (code "40") (name "Net-(U1-PD3(INT1))") (class "Default")
      (node (ref "JP121") (pin "1") (pinfunction "1_1") (pintype "passive"))
      (node (ref "U1") (pin "5") (pinfunction "PD3(INT1)_5") (pintype "bidirectional"))
    )
    (net (code "41") (name "Net-(U1-PD7(AIN1))") (class "Default")
      (node (ref "R131") (pin "2") (pinfunction "2_2") (pintype "passive"))
      (node (ref "R132") (pin "1") (pinfunction "1_1") (pintype "passive"))
      (node (ref "U1") (pin "13") (pinfunction "PD7(AIN1)_13") (pintype "bidirectional"))
    )
    (net (code "42") (name "Net-(U2-GND0)") (class "Default")
      (node (ref "SJ201") (pin "2") (pinfunction "2_2") (pintype "passive"))
      (node (ref "U2") (pin "12") (pinfunction "GND_12") (pintype "power_in"))
      (node (ref "U2") (pin "27") (pinfunction "GND1_27") (pintype "power_in"))
      (node (ref "U2") (pin "34") (pinfunction "GND_34") (pintype "power_in"))
      (node (ref "U2") (pin "5") (pinfunction "GND0_5") (pintype "power_in"))
    )
    (net (code "43") (name "Net-(U2-IOA0)") (class "Default")
      (node (ref "R931") (pin "1") (pinfunction "1_1") (pintype "passive"))
      (node (ref "U2") (pin "40") (pinfunction "IOA0_40") (pintype "bidirectional"))
    )
    (net (code "44") (name "Net-(U2-IOA4)") (class "Default")
      (node (ref "CON4") (pin "5") (pinfunction "5_5") (pintype "passive"))
      (node (ref "CON5") (pin "6") (pinfunction "6_6") (pintype "passive"))
      (node (ref "JP111") (pin "2") (pinfunction "2_2") (pintype "passive"))
      (node (ref "R121") (pin "2") (pinfunction "2_2") (pintype "passive"))
      (node (ref "U2") (pin "44") (pinfunction "IOA4_44") (pintype "bidirectional"))
    )
    (net (code "45") (name "Net-(U2-IOA7)") (class "Default")
      (node (ref "R201") (pin "2") (pinfunction "2_2") (pintype "passive"))
      (node (ref "U2") (pin "4") (pinfunction "IOA7_4") (pintype "bidirectional"))
    )
    (net (code "46") (name "Net-(U2-IOB15)") (class "Default")
      (node (ref "U2") (pin "38") (pinfunction "IOB15_38") (pintype "bidirectional"))
      (node (ref "U3") (pin "1") (pinfunction "A_1") (pintype "input"))
    )
    (net (code "47") (name "Net-(U2-TCK)") (class "Default")
      (node (ref "CON5") (pin "1") (pinfunction "1_1") (pintype "passive"))
      (node (ref "U2") (pin "10") (pinfunction "TCK_10") (pintype "input"))
    )
    (net (code "48") (name "Net-(U2-TDI)") (class "Default")
      (node (ref "CON5") (pin "9") (pinfunction "9_9") (pintype "passive"))
      (node (ref "U2") (pin "1") (pinfunction "TDI_1") (pintype "input"))
    )
    (net (code "49") (name "Net-(U2-TDO)") (class "Default")
      (node (ref "CON5") (pin "3") (pinfunction "3_3") (pintype "passive"))
      (node (ref "U2") (pin "32") (pinfunction "TDO_32") (pintype "output"))
    )
    (net (code "50") (name "Net-(U2-TMS)") (class "Default")
      (node (ref "CON5") (pin "5") (pinfunction "5_5") (pintype "passive"))
      (node (ref "U2") (pin "23") (pinfunction "TMS_23") (pintype "input"))
    )
    (net (code "51") (name "Net-(U2-VCCO0)") (class "Default")
      (node (ref "SJ202") (pin "1") (pinfunction "1_1") (pintype "passive"))
      (node (ref "U2") (pin "11") (pinfunction "VCC_3V3_11") (pintype "power_in"))
      (node (ref "U2") (pin "28") (pinfunction "VCCO1_28") (pintype "power_in"))
      (node (ref "U2") (pin "33") (pinfunction "VCC_3V3_33") (pintype "power_in"))
      (node (ref "U2") (pin "6") (pinfunction "VCCO0_6") (pintype "power_in"))
    )
    (net (code "52") (name "Net-(U3A-C)") (class "Default")
      (node (ref "C301") (pin "1") (pinfunction "1_1") (pintype "passive"))
      (node (ref "U3") (pin "14") (pinfunction "C_14") (pintype "input"))
    )
    (net (code "53") (name "Net-(U3A-R{slash}C)") (class "Default")
      (node (ref "C301") (pin "2") (pinfunction "2_2") (pintype "passive"))
      (node (ref "R301") (pin "1") (pinfunction "1_1") (pintype "passive"))
      (node (ref "U3") (pin "15") (pinfunction "R/C_15") (pintype "input"))
    )
    (net (code "54") (name "Net-(U3B-C)") (class "Default")
      (node (ref "C311") (pin "1") (pinfunction "1_1") (pintype "passive"))
      (node (ref "U3") (pin "6") (pinfunction "C_6") (pintype "input"))
    )
    (net (code "55") (name "Net-(U3B-R{slash}C)") (class "Default")
      (node (ref "C311") (pin "2") (pinfunction "2_2") (pintype "passive"))
      (node (ref "R311") (pin "1") (pinfunction "1_1") (pintype "passive"))
      (node (ref "U3") (pin "7") (pinfunction "R/C_7") (pintype "input"))
    )
    (net (code "56") (name "Net-(U5-+IN)") (class "Default")
      (node (ref "C411") (pin "1") (pinfunction "1_1") (pintype "passive"))
      (node (ref "R411") (pin "2") (pinfunction "2_2") (pintype "passive"))
      (node (ref "R412") (pin "2") (pinfunction "2_2") (pintype "passive"))
      (node (ref "U5") (pin "3") (pinfunction "+IN_3") (pintype "input"))
    )
    (net (code "57") (name "Net-(U5--IN)") (class "Default")
      (node (ref "R501") (pin "2") (pinfunction "2_2") (pintype "passive"))
      (node (ref "U5") (pin "4") (pinfunction "-IN_4") (pintype "input"))
    )
    (net (code "58") (name "Net-(U6-EN)") (class "Default")
      (node (ref "R601") (pin "2") (pinfunction "2_2") (pintype "passive"))
      (node (ref "U6") (pin "4") (pinfunction "EN_4") (pintype "input"))
    )
    (net (code "59") (name "Net-(U6-FB)") (class "Default")
      (node (ref "R611") (pin "2") (pinfunction "2_2") (pintype "passive"))
      (node (ref "R612") (pin "2") (pinfunction "2_2") (pintype "passive"))
      (node (ref "U6") (pin "3") (pinfunction "FB_3") (pintype "input"))
    )
    (net (code "60") (name "Net-(U6-SW)") (class "Default")
      (node (ref "D611") (pin "C") (pinfunction "C_C") (pintype "passive"))
      (node (ref "L611") (pin "2") (pinfunction "2_2") (pintype "passive"))
      (node (ref "U6") (pin "1") (pinfunction "SW_1") (pintype "output"))
    )
    (net (code "61") (name "Net-(U7-VCC_3V0)") (class "Default")
      (node (ref "C791") (pin "1") (pinfunction "1_1") (pintype "passive"))
      (node (ref "D701") (pin "C") (pinfunction "C_C") (pintype "passive"))
      (node (ref "R701") (pin "2") (pinfunction "2_2") (pintype "passive"))
      (node (ref "U7") (pin "4") (pinfunction "VCC_3V0_4") (pintype "power_in"))
    )
    (net (code "62") (name "Net-(U8-RF_IN)") (class "Default")
      (node (ref "CON7") (pin "1") (pinfunction "1_1") (pintype "passive"))
      (node (ref "LFP811") (pin "1") (pinfunction "1_1") (pintype "passive"))
      (node (ref "U8") (pin "21") (pinfunction "RF_IN_21") (pintype "input"))
    )
    (net (code "63") (name "Net-(U8-VCC_RF)") (class "Default")
      (node (ref "LFP811") (pin "2") (pinfunction "2_2") (pintype "passive"))
      (node (ref "U8") (pin "19") (pinfunction "VCC_RF_19") (pintype "output"))
    )
    (net (code "64") (name "PHASE_ERROR") (class "Default")
      (node (ref "D401") (pin "C") (pinfunction "C_C") (pintype "passive"))
      (node (ref "R411") (pin "1") (pinfunction "1_1") (pintype "passive"))
    )
    (net (code "65") (name "PHASE_RSFF") (class "Default")
      (node (ref "D401") (pin "A") (pinfunction "A_A") (pintype "passive"))
      (node (ref "U2") (pin "35") (pinfunction "IOB12_35") (pintype "bidirectional"))
    )
    (net (code "66") (name "SYNC_IN") (class "Default")
      (node (ref "U2") (pin "37") (pinfunction "IOB14_37") (pintype "bidirectional"))
      (node (ref "U3") (pin "13") (pinfunction "Q_13") (pintype "output"))
    )
    (net (code "67") (name "VCC") (class "Default")
      (node (ref "C191") (pin "1") (pinfunction "1_1") (pintype "passive"))
      (node (ref "C211") (pin "1") (pinfunction "1_1") (pintype "passive"))
      (node (ref "C391") (pin "1") (pinfunction "1_1") (pintype "passive"))
      (node (ref "C491") (pin "1") (pinfunction "1_1") (pintype "passive"))
      (node (ref "C591") (pin "1") (pinfunction "1_1") (pintype "passive"))
      (node (ref "C911") (pin "1") (pinfunction "1_1") (pintype "passive"))
      (node (ref "C912") (pin "1") (pinfunction "1_1") (pintype "passive"))
      (node (ref "CON5") (pin "7") (pinfunction "7_7") (pintype "passive"))
      (node (ref "CON6") (pin "3") (pinfunction "3_3") (pintype "passive"))
      (node (ref "JP941") (pin "1") (pinfunction "1_1") (pintype "passive"))
      (node (ref "L101") (pin "2") (pinfunction "2_2") (pintype "passive"))
      (node (ref "R111") (pin "1") (pinfunction "1_1") (pintype "passive"))
      (node (ref "R132") (pin "2") (pinfunction "2_2") (pintype "passive"))
      (node (ref "R301") (pin "2") (pinfunction "2_2") (pintype "passive"))
      (node (ref "R311") (pin "2") (pinfunction "2_2") (pintype "passive"))
      (node (ref "R601") (pin "1") (pinfunction "1_1") (pintype "passive"))
      (node (ref "R951") (pin "2") (pinfunction "2_2") (pintype "passive"))
      (node (ref "RPOLY1") (pin "2") (pinfunction "2_2") (pintype "passive"))
      (node (ref "U1") (pin "7") (pinfunction "VCC_7") (pintype "bidirectional"))
      (node (ref "U3") (pin "10") (pinfunction "B_10") (pintype "input"))
      (node (ref "U3") (pin "11") (pinfunction "R_11") (pintype "input"))
      (node (ref "U3") (pin "16") (pinfunction "VCC_16") (pintype "power_in"))
      (node (ref "U3") (pin "2") (pinfunction "B_2") (pintype "input"))
      (node (ref "U3") (pin "3") (pinfunction "R_3") (pintype "input"))
      (node (ref "U5") (pin "5") (pinfunction "V+_5") (pintype "power_in"))
      (node (ref "U6") (pin "5") (pinfunction "VIN_5") (pintype "power_in"))
    )
    (net (code "68") (name "unconnected-(CON5-Pad8)") (class "Default")
      (node (ref "CON5") (pin "8") (pinfunction "8_8") (pintype "passive"))
    )
    (net (code "69") (name "unconnected-(U1-PB7(XTAL2{slash}TOSC2)-Pad10)") (class "Default")
      (node (ref "U1") (pin "10") (pinfunction "PB7(XTAL2/TOSC2)_10") (pintype "bidirectional"))
    )
    (net (code "70") (name "unconnected-(U2-IOA1-Pad41)") (class "Default")
      (node (ref "U2") (pin "41") (pinfunction "IOA1_41") (pintype "bidirectional"))
    )
    (net (code "71") (name "unconnected-(U2-IOA5-Pad2)") (class "Default")
      (node (ref "U2") (pin "2") (pinfunction "IOA5_2") (pintype "bidirectional"))
    )
    (net (code "72") (name "unconnected-(U2-IOA13-Pad14)") (class "Default")
      (node (ref "U2") (pin "14") (pinfunction "IOA13_14") (pintype "bidirectional"))
    )
    (net (code "73") (name "unconnected-(U2-IOA14-Pad15)") (class "Default")
      (node (ref "U2") (pin "15") (pinfunction "IOA14_15") (pintype "bidirectional"))
    )
    (net (code "74") (name "unconnected-(U2-IOB0-Pad18)") (class "Default")
      (node (ref "U2") (pin "18") (pinfunction "IOB0_18") (pintype "bidirectional"))
    )
    (net (code "75") (name "unconnected-(U2-IOB1-Pad19)") (class "Default")
      (node (ref "U2") (pin "19") (pinfunction "IOB1_19") (pintype "bidirectional"))
    )
    (net (code "76") (name "unconnected-(U2-IOB2-Pad20)") (class "Default")
      (node (ref "U2") (pin "20") (pinfunction "IOB2_20") (pintype "bidirectional"))
    )
    (net (code "77") (name "unconnected-(U2-IOB3-Pad21)") (class "Default")
      (node (ref "U2") (pin "21") (pinfunction "IOB3_21") (pintype "bidirectional"))
    )
    (net (code "78") (name "unconnected-(U2-IOB4-Pad22)") (class "Default")
      (node (ref "U2") (pin "22") (pinfunction "IOB4_22") (pintype "bidirectional"))
    )
    (net (code "79") (name "unconnected-(U2-IOB5-Pad24)") (class "Default")
      (node (ref "U2") (pin "24") (pinfunction "IOB5_24") (pintype "bidirectional"))
    )
    (net (code "80") (name "unconnected-(U2-IOB6-Pad25)") (class "Default")
      (node (ref "U2") (pin "25") (pinfunction "IOB6_25") (pintype "bidirectional"))
    )
    (net (code "81") (name "unconnected-(U2-IOB7-Pad26)") (class "Default")
      (node (ref "U2") (pin "26") (pinfunction "IOB7_26") (pintype "bidirectional"))
    )
    (net (code "82") (name "unconnected-(U2-IOB8-Pad29)") (class "Default")
      (node (ref "U2") (pin "29") (pinfunction "IOB8_29") (pintype "bidirectional"))
    )
    (net (code "83") (name "unconnected-(U2-IOB9-Pad30)") (class "Default")
      (node (ref "U2") (pin "30") (pinfunction "IOB9_30") (pintype "bidirectional"))
    )
    (net (code "84") (name "unconnected-(U3A-~{Q}-Pad4)") (class "Default")
      (node (ref "U3") (pin "4") (pinfunction "~{Q}_4") (pintype "output"))
    )
    (net (code "85") (name "unconnected-(U3B-~{Q}-Pad12)") (class "Default")
      (node (ref "U3") (pin "12") (pinfunction "~{Q}_12") (pintype "output"))
    )
    (net (code "86") (name "unconnected-(U8-BOOTSEL-Pad18)") (class "Default")
      (node (ref "U8") (pin "18") (pinfunction "BOOTSEL_18") (pintype "input"))
    )
    (net (code "87") (name "unconnected-(U8-RESERVED-Pad1)") (class "Default")
      (node (ref "U8") (pin "1") (pinfunction "RESERVED_1") (pintype "no_connect"))
    )
    (net (code "88") (name "unconnected-(U8-RESERVED-Pad2)") (class "Default")
      (node (ref "U8") (pin "2") (pinfunction "RESERVED_2") (pintype "no_connect"))
    )
    (net (code "89") (name "unconnected-(U8-RESERVED-Pad7)") (class "Default")
      (node (ref "U8") (pin "7") (pinfunction "RESERVED_7") (pintype "no_connect"))
    )
    (net (code "90") (name "unconnected-(U8-RESERVED-Pad8)") (class "Default")
      (node (ref "U8") (pin "8") (pinfunction "RESERVED_8") (pintype "no_connect"))
    )
    (net (code "91") (name "unconnected-(U8-RESERVED-Pad9)") (class "Default")
      (node (ref "U8") (pin "9") (pinfunction "RESERVED_9") (pintype "no_connect"))
    )
    (net (code "92") (name "unconnected-(U8-RESERVED-Pad10)") (class "Default")
      (node (ref "U8") (pin "10") (pinfunction "RESERVED_10") (pintype "no_connect"))
    )
    (net (code "93") (name "unconnected-(U8-RESERVED-Pad14)") (class "Default")
      (node (ref "U8") (pin "14") (pinfunction "RESERVED_14") (pintype "no_connect"))
    )
    (net (code "94") (name "unconnected-(U8-RESERVED-Pad15)") (class "Default")
      (node (ref "U8") (pin "15") (pinfunction "RESERVED_15") (pintype "no_connect"))
    )
    (net (code "95") (name "unconnected-(U8-RESERVED-Pad16)") (class "Default")
      (node (ref "U8") (pin "16") (pinfunction "RESERVED_16") (pintype "no_connect"))
    )
  )
)
